# uC.net
KiCad netlist of a schematic drawn in Altium Designer
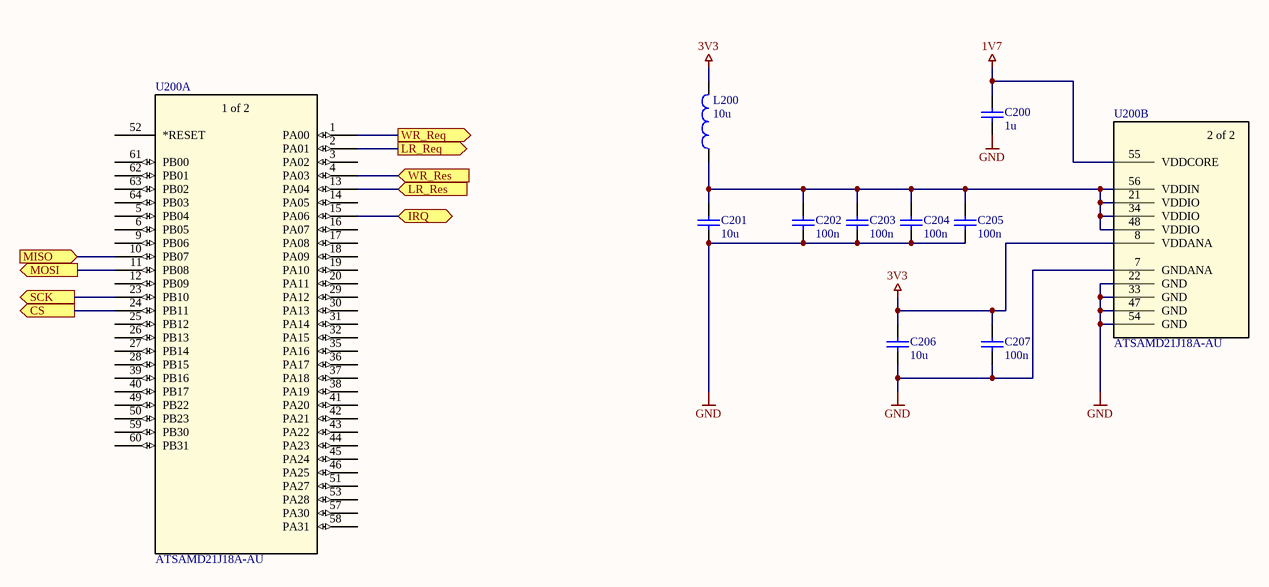
[diagram p0: uC.SchDoc]

(export (version "E")
  (design (tool "Eeschema 10.0.6"))
  (components
    (comp (ref "C200")
      (value "1u")
      (description "Capacitor")
      (libsource (lib "Simulation Generic Components") (part "Capacitor"))
    )
    (comp (ref "C201")
      (value "10u")
      (description "Capacitor")
      (libsource (lib "Simulation Generic Components") (part "Capacitor"))
    )
    (comp (ref "C202")
      (value "100n")
      (description "Capacitor")
      (libsource (lib "Simulation Generic Components") (part "Capacitor"))
    )
    (comp (ref "C203")
      (value "100n")
      (description "Capacitor")
      (libsource (lib "Simulation Generic Components") (part "Capacitor"))
    )
    (comp (ref "C204")
      (value "100n")
      (description "Capacitor")
      (libsource (lib "Simulation Generic Components") (part "Capacitor"))
    )
    (comp (ref "C205")
      (value "100n")
      (description "Capacitor")
      (libsource (lib "Simulation Generic Components") (part "Capacitor"))
    )
    (comp (ref "C206")
      (value "10u")
      (description "Capacitor")
      (libsource (lib "Simulation Generic Components") (part "Capacitor"))
    )
    (comp (ref "C207")
      (value "100n")
      (description "Capacitor")
      (libsource (lib "Simulation Generic Components") (part "Capacitor"))
    )
    (comp (ref "L200")
      (value "10u")
      (description "Inductor")
      (libsource (lib "Simulation Generic Components") (part "Inductor"))
    )
    (comp (ref "U200")
      (value "ATSAMD21J18A-AU")
      (footprint "TQFP64_10x10MC_MCH")
      (description "No Description Available")
      (libsource (lib "ATSAMD21J18A-AU") (part "ATSAMD21J18A-AU"))
    )
  )
  (nets
    (net (code "1") (name "/CS") (class "Default")
      (node (ref "U200") (pin "24") (pinfunction "PB11_24") (pintype "bidirectional"))
    )
    (net (code "2") (name "/IRQ") (class "Default")
      (node (ref "U200") (pin "15") (pinfunction "PA06_15") (pintype "bidirectional"))
    )
    (net (code "3") (name "/LR_Req") (class "Default")
      (node (ref "U200") (pin "2") (pinfunction "PA01_2") (pintype "bidirectional"))
    )
    (net (code "4") (name "/LR_Res") (class "Default")
      (node (ref "U200") (pin "13") (pinfunction "PA04_13") (pintype "bidirectional"))
    )
    (net (code "5") (name "/MISO") (class "Default")
      (node (ref "U200") (pin "10") (pinfunction "PB07_10") (pintype "bidirectional"))
    )
    (net (code "6") (name "/MOSI") (class "Default")
      (node (ref "U200") (pin "11") (pinfunction "PB08_11") (pintype "bidirectional"))
    )
    (net (code "7") (name "/SCK") (class "Default")
      (node (ref "U200") (pin "23") (pinfunction "PB10_23") (pintype "bidirectional"))
    )
    (net (code "8") (name "/WR_Req") (class "Default")
      (node (ref "U200") (pin "1") (pinfunction "PA00_1") (pintype "bidirectional"))
    )
    (net (code "9") (name "/WR_Res") (class "Default")
      (node (ref "U200") (pin "4") (pinfunction "PA03_4") (pintype "bidirectional"))
    )
    (net (code "10") (name "1V7") (class "Default")
      (node (ref "C200") (pin "2") (pinfunction "2_2") (pintype "passive"))
      (node (ref "U200") (pin "55") (pinfunction "VDDCORE_55") (pintype "power_in"))
    )
    (net (code "11") (name "3V3") (class "Default")
      (node (ref "C206") (pin "2") (pinfunction "2_2") (pintype "passive"))
      (node (ref "C207") (pin "2") (pinfunction "2_2") (pintype "passive"))
      (node (ref "L200") (pin "2") (pinfunction "2_2") (pintype "passive"))
      (node (ref "U200") (pin "8") (pinfunction "VDDANA_8") (pintype "power_in"))
    )
    (net (code "12") (name "GND") (class "Default")
      (node (ref "C200") (pin "1") (pinfunction "1_1") (pintype "passive"))
      (node (ref "C201") (pin "1") (pinfunction "1_1") (pintype "passive"))
      (node (ref "C202") (pin "1") (pinfunction "1_1") (pintype "passive"))
      (node (ref "C203") (pin "1") (pinfunction "1_1") (pintype "passive"))
      (node (ref "C204") (pin "1") (pinfunction "1_1") (pintype "passive"))
      (node (ref "C205") (pin "1") (pinfunction "1_1") (pintype "passive"))
      (node (ref "C206") (pin "1") (pinfunction "1_1") (pintype "passive"))
      (node (ref "C207") (pin "1") (pinfunction "1_1") (pintype "passive"))
      (node (ref "U200") (pin "22") (pinfunction "GND_22") (pintype "power_in"))
      (node (ref "U200") (pin "33") (pinfunction "GND_33") (pintype "power_in"))
      (node (ref "U200") (pin "47") (pinfunction "GND_47") (pintype "power_in"))
      (node (ref "U200") (pin "54") (pinfunction "GND_54") (pintype "power_in"))
      (node (ref "U200") (pin "7") (pinfunction "GNDANA_7") (pintype "power_in"))
    )
    (net (code "13") (name "Net-(U200B-VDDIN)") (class "Default")
      (node (ref "C201") (pin "2") (pinfunction "2_2") (pintype "passive"))
      (node (ref "C202") (pin "2") (pinfunction "2_2") (pintype "passive"))
      (node (ref "C203") (pin "2") (pinfunction "2_2") (pintype "passive"))
      (node (ref "C204") (pin "2") (pinfunction "2_2") (pintype "passive"))
      (node (ref "C205") (pin "2") (pinfunction "2_2") (pintype "passive"))
      (node (ref "L200") (pin "1") (pinfunction "1_1") (pintype "passive"))
      (node (ref "U200") (pin "21") (pinfunction "VDDIO_21") (pintype "power_in"))
      (node (ref "U200") (pin "34") (pinfunction "VDDIO_34") (pintype "power_in"))
      (node (ref "U200") (pin "48") (pinfunction "VDDIO_48") (pintype "power_in"))
      (node (ref "U200") (pin "56") (pinfunction "VDDIN_56") (pintype "power_in"))
    )
    (net (code "14") (name "unconnected-(U200A-*RESET-Pad52)") (class "Default")
      (node (ref "U200") (pin "52") (pinfunction "*RESET_52") (pintype "passive"))
    )
    (net (code "15") (name "unconnected-(U200A-PA02-Pad3)") (class "Default")
      (node (ref "U200") (pin "3") (pinfunction "PA02_3") (pintype "bidirectional"))
    )
    (net (code "16") (name "unconnected-(U200A-PA05-Pad14)") (class "Default")
      (node (ref "U200") (pin "14") (pinfunction "PA05_14") (pintype "bidirectional"))
    )
    (net (code "17") (name "unconnected-(U200A-PA07-Pad16)") (class "Default")
      (node (ref "U200") (pin "16") (pinfunction "PA07_16") (pintype "bidirectional"))
    )
    (net (code "18") (name "unconnected-(U200A-PA08-Pad17)") (class "Default")
      (node (ref "U200") (pin "17") (pinfunction "PA08_17") (pintype "bidirectional"))
    )
    (net (code "19") (name "unconnected-(U200A-PA09-Pad18)") (class "Default")
      (node (ref "U200") (pin "18") (pinfunction "PA09_18") (pintype "bidirectional"))
    )
    (net (code "20") (name "unconnected-(U200A-PA10-Pad19)") (class "Default")
      (node (ref "U200") (pin "19") (pinfunction "PA10_19") (pintype "bidirectional"))
    )
    (net (code "21") (name "unconnected-(U200A-PA11-Pad20)") (class "Default")
      (node (ref "U200") (pin "20") (pinfunction "PA11_20") (pintype "bidirectional"))
    )
    (net (code "22") (name "unconnected-(U200A-PA12-Pad29)") (class "Default")
      (node (ref "U200") (pin "29") (pinfunction "PA12_29") (pintype "bidirectional"))
    )
    (net (code "23") (name "unconnected-(U200A-PA13-Pad30)") (class "Default")
      (node (ref "U200") (pin "30") (pinfunction "PA13_30") (pintype "bidirectional"))
    )
    (net (code "24") (name "unconnected-(U200A-PA14-Pad31)") (class "Default")
      (node (ref "U200") (pin "31") (pinfunction "PA14_31") (pintype "bidirectional"))
    )
    (net (code "25") (name "unconnected-(U200A-PA15-Pad32)") (class "Default")
      (node (ref "U200") (pin "32") (pinfunction "PA15_32") (pintype "bidirectional"))
    )
    (net (code "26") (name "unconnected-(U200A-PA16-Pad35)") (class "Default")
      (node (ref "U200") (pin "35") (pinfunction "PA16_35") (pintype "bidirectional"))
    )
    (net (code "27") (name "unconnected-(U200A-PA17-Pad36)") (class "Default")
      (node (ref "U200") (pin "36") (pinfunction "PA17_36") (pintype "bidirectional"))
    )
    (net (code "28") (name "unconnected-(U200A-PA18-Pad37)") (class "Default")
      (node (ref "U200") (pin "37") (pinfunction "PA18_37") (pintype "bidirectional"))
    )
    (net (code "29") (name "unconnected-(U200A-PA19-Pad38)") (class "Default")
      (node (ref "U200") (pin "38") (pinfunction "PA19_38") (pintype "bidirectional"))
    )
    (net (code "30") (name "unconnected-(U200A-PA20-Pad41)") (class "Default")
      (node (ref "U200") (pin "41") (pinfunction "PA20_41") (pintype "bidirectional"))
    )
    (net (code "31") (name "unconnected-(U200A-PA21-Pad42)") (class "Default")
      (node (ref "U200") (pin "42") (pinfunction "PA21_42") (pintype "bidirectional"))
    )
    (net (code "32") (name "unconnected-(U200A-PA22-Pad43)") (class "Default")
      (node (ref "U200") (pin "43") (pinfunction "PA22_43") (pintype "bidirectional"))
    )
    (net (code "33") (name "unconnected-(U200A-PA23-Pad44)") (class "Default")
      (node (ref "U200") (pin "44") (pinfunction "PA23_44") (pintype "bidirectional"))
    )
    (net (code "34") (name "unconnected-(U200A-PA24-Pad45)") (class "Default")
      (node (ref "U200") (pin "45") (pinfunction "PA24_45") (pintype "bidirectional"))
    )
    (net (code "35") (name "unconnected-(U200A-PA25-Pad46)") (class "Default")
      (node (ref "U200") (pin "46") (pinfunction "PA25_46") (pintype "bidirectional"))
    )
    (net (code "36") (name "unconnected-(U200A-PA27-Pad51)") (class "Default")
      (node (ref "U200") (pin "51") (pinfunction "PA27_51") (pintype "bidirectional"))
    )
    (net (code "37") (name "unconnected-(U200A-PA28-Pad53)") (class "Default")
      (node (ref "U200") (pin "53") (pinfunction "PA28_53") (pintype "bidirectional"))
    )
    (net (code "38") (name "unconnected-(U200A-PA30-Pad57)") (class "Default")
      (node (ref "U200") (pin "57") (pinfunction "PA30_57") (pintype "bidirectional"))
    )
    (net (code "39") (name "unconnected-(U200A-PA31-Pad58)") (class "Default")
      (node (ref "U200") (pin "58") (pinfunction "PA31_58") (pintype "bidirectional"))
    )
    (net (code "40") (name "unconnected-(U200A-PB00-Pad61)") (class "Default")
      (node (ref "U200") (pin "61") (pinfunction "PB00_61") (pintype "bidirectional"))
    )
    (net (code "41") (name "unconnected-(U200A-PB01-Pad62)") (class "Default")
      (node (ref "U200") (pin "62") (pinfunction "PB01_62") (pintype "bidirectional"))
    )
    (net (code "42") (name "unconnected-(U200A-PB02-Pad63)") (class "Default")
      (node (ref "U200") (pin "63") (pinfunction "PB02_63") (pintype "bidirectional"))
    )
    (net (code "43") (name "unconnected-(U200A-PB03-Pad64)") (class "Default")
      (node (ref "U200") (pin "64") (pinfunction "PB03_64") (pintype "bidirectional"))
    )
    (net (code "44") (name "unconnected-(U200A-PB04-Pad5)") (class "Default")
      (node (ref "U200") (pin "5") (pinfunction "PB04_5") (pintype "bidirectional"))
    )
    (net (code "45") (name "unconnected-(U200A-PB05-Pad6)") (class "Default")
      (node (ref "U200") (pin "6") (pinfunction "PB05_6") (pintype "bidirectional"))
    )
    (net (code "46") (name "unconnected-(U200A-PB06-Pad9)") (class "Default")
      (node (ref "U200") (pin "9") (pinfunction "PB06_9") (pintype "bidirectional"))
    )
    (net (code "47") (name "unconnected-(U200A-PB09-Pad12)") (class "Default")
      (node (ref "U200") (pin "12") (pinfunction "PB09_12") (pintype "bidirectional"))
    )
    (net (code "48") (name "unconnected-(U200A-PB12-Pad25)") (class "Default")
      (node (ref "U200") (pin "25") (pinfunction "PB12_25") (pintype "bidirectional"))
    )
    (net (code "49") (name "unconnected-(U200A-PB13-Pad26)") (class "Default")
      (node (ref "U200") (pin "26") (pinfunction "PB13_26") (pintype "bidirectional"))
    )
    (net (code "50") (name "unconnected-(U200A-PB14-Pad27)") (class "Default")
      (node (ref "U200") (pin "27") (pinfunction "PB14_27") (pintype "bidirectional"))
    )
    (net (code "51") (name "unconnected-(U200A-PB15-Pad28)") (class "Default")
      (node (ref "U200") (pin "28") (pinfunction "PB15_28") (pintype "bidirectional"))
    )
    (net (code "52") (name "unconnected-(U200A-PB16-Pad39)") (class "Default")
      (node (ref "U200") (pin "39") (pinfunction "PB16_39") (pintype "bidirectional"))
    )
    (net (code "53") (name "unconnected-(U200A-PB17-Pad40)") (class "Default")
      (node (ref "U200") (pin "40") (pinfunction "PB17_40") (pintype "bidirectional"))
    )
    (net (code "54") (name "unconnected-(U200A-PB22-Pad49)") (class "Default")
      (node (ref "U200") (pin "49") (pinfunction "PB22_49") (pintype "bidirectional"))
    )
    (net (code "55") (name "unconnected-(U200A-PB23-Pad50)") (class "Default")
      (node (ref "U200") (pin "50") (pinfunction "PB23_50") (pintype "bidirectional"))
    )
    (net (code "56") (name "unconnected-(U200A-PB30-Pad59)") (class "Default")
      (node (ref "U200") (pin "59") (pinfunction "PB30_59") (pintype "bidirectional"))
    )
    (net (code "57") (name "unconnected-(U200A-PB31-Pad60)") (class "Default")
      (node (ref "U200") (pin "60") (pinfunction "PB31_60") (pintype "bidirectional"))
    )
  )
)
